# Analog_Board.net
KiCad netlist of a schematic drawn in EAGLE
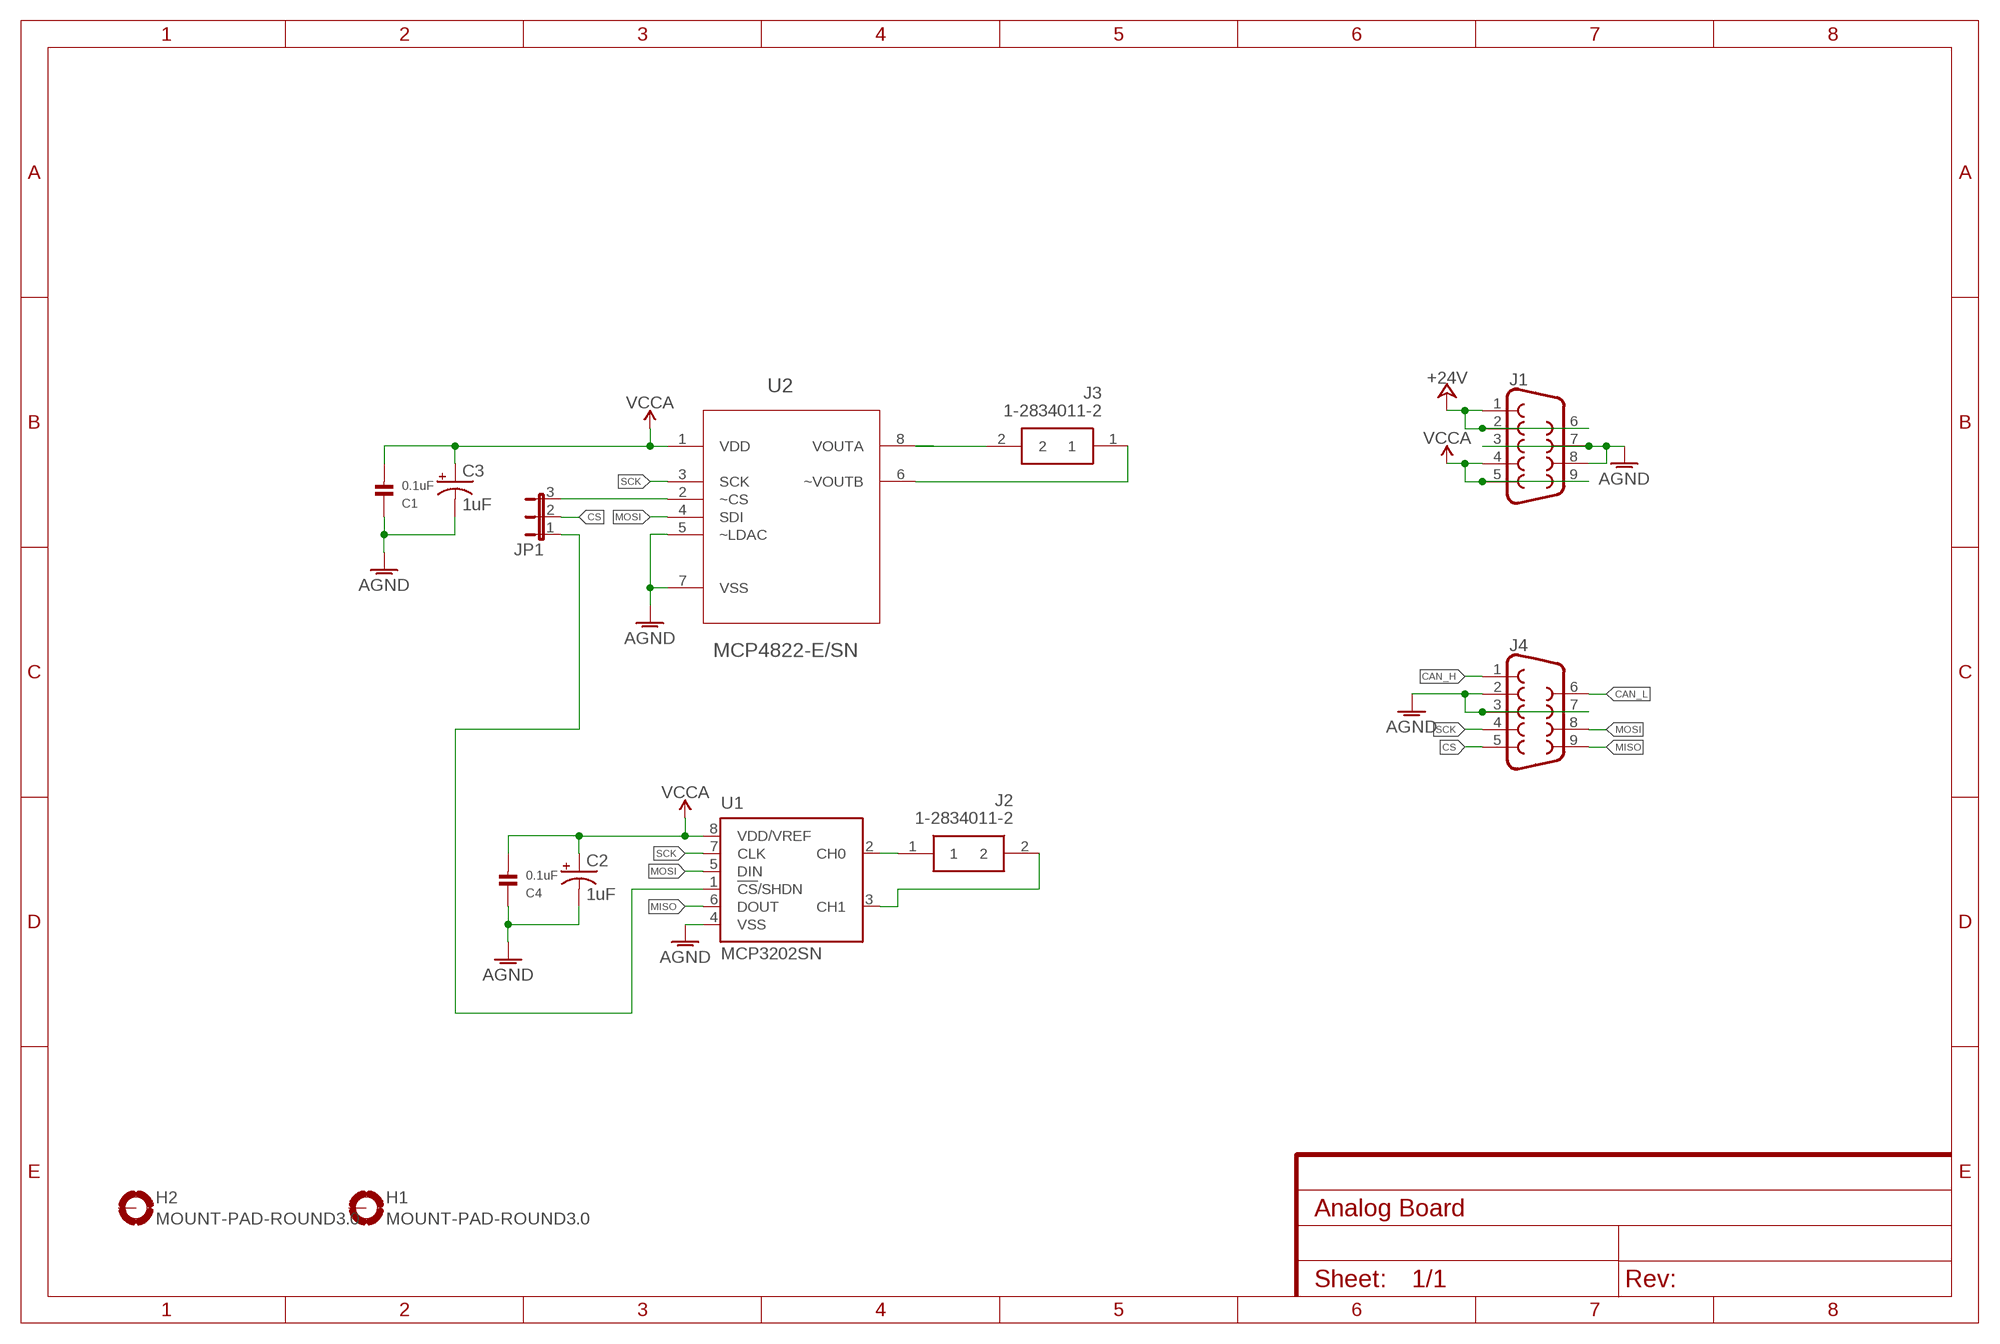
[diagram p0: schematic, sheet 1]

(export (version "E")
  (design (tool "Eeschema 10.0.6"))
  (components
    (comp (ref "C1")
      (value "0.1uF")
      (footprint "eagle-import:0805_NOTHERMALS")
      (libsource (lib "eagle-import") (part "CAP_CERAMIC0805-NOTHERMALS"))
    )
    (comp (ref "C2")
      (value "1uF")
      (footprint "eagle-import:PANASONIC_B")
      (libsource (lib "eagle-import") (part "CPOL-USB"))
    )
    (comp (ref "C3")
      (value "1uF")
      (footprint "eagle-import:PANASONIC_B")
      (libsource (lib "eagle-import") (part "CPOL-USB"))
    )
    (comp (ref "C4")
      (value "0.1uF")
      (footprint "eagle-import:0805_NOTHERMALS")
      (libsource (lib "eagle-import") (part "CAP_CERAMIC0805-NOTHERMALS"))
    )
    (comp (ref "H1")
      (value "MOUNT-PAD-ROUND3.0")
      (footprint "eagle-import:3,0-PAD")
      (libsource (lib "eagle-import") (part "MOUNT-PAD-ROUND3.0"))
    )
    (comp (ref "H2")
      (value "MOUNT-PAD-ROUND3.0")
      (footprint "eagle-import:3,0-PAD")
      (libsource (lib "eagle-import") (part "MOUNT-PAD-ROUND3.0"))
    )
    (comp (ref "J1")
      (value "DB9FEMALE")
      (footprint "eagle-import:DB9")
      (libsource (lib "eagle-import") (part "DB9FEMALE"))
    )
    (comp (ref "J2")
      (value "1-2834011-2")
      (footprint "eagle-import:128340112")
      (fields (field (name "RS_PART_NUMBER") "1649131"))
      (libsource (lib "eagle-import") (part "1-2834011-2"))
    )
    (comp (ref "J3")
      (value "1-2834011-2")
      (footprint "eagle-import:128340112")
      (fields (field (name "RS_PART_NUMBER") "1649131"))
      (libsource (lib "eagle-import") (part "1-2834011-2"))
    )
    (comp (ref "J4")
      (value "DB9FEMALE")
      (footprint "eagle-import:DB9")
      (libsource (lib "eagle-import") (part "DB9FEMALE"))
    )
    (comp (ref "JP1")
      (value "JP2W")
      (footprint "eagle-import:JP2W")
      (libsource (lib "eagle-import") (part "JP2W"))
    )
    (comp (ref "U1")
      (value "MCP3202SN")
      (footprint "eagle-import:SO-08")
      (fields (field (name "MF") "MICROCHIP") (field (name "MPN") "MCP3202-CI/SN"))
      (libsource (lib "eagle-import") (part "MCP3202SN"))
    )
    (comp (ref "U2")
      (value "MCP4822-E/SN")
      (footprint "eagle-import:SOIC8-N_MC")
      (fields (field (name "MF") "Microchip"))
      (libsource (lib "eagle-import") (part "MCP4822-E/SN"))
    )
  )
  (nets
    (net (code "1") (name "+24V") (class "Default")
      (node (ref "J1") (pin "1") (pinfunction "1_1") (pintype "passive"))
      (node (ref "J1") (pin "2") (pinfunction "2_2") (pintype "passive"))
      (node (ref "J1") (pin "6") (pinfunction "6_6") (pintype "passive"))
    )
    (net (code "2") (name "AGND") (class "Default")
      (node (ref "C1") (pin "1") (pinfunction "P$1_1") (pintype "passive"))
      (node (ref "C2") (pin "-") (pinfunction "-_-") (pintype "passive"))
      (node (ref "C3") (pin "-") (pinfunction "-_-") (pintype "passive"))
      (node (ref "C4") (pin "1") (pinfunction "P$1_1") (pintype "passive"))
      (node (ref "J1") (pin "3") (pinfunction "3_3") (pintype "passive"))
      (node (ref "J1") (pin "7") (pinfunction "7_7") (pintype "passive"))
      (node (ref "J1") (pin "8") (pinfunction "8_8") (pintype "passive"))
      (node (ref "J4") (pin "2") (pinfunction "2_2") (pintype "passive"))
      (node (ref "J4") (pin "3") (pinfunction "3_3") (pintype "passive"))
      (node (ref "J4") (pin "7") (pinfunction "7_7") (pintype "passive"))
      (node (ref "U1") (pin "4") (pinfunction "VSS_4") (pintype "input"))
      (node (ref "U2") (pin "5") (pinfunction "~{LDAC}_5") (pintype "input"))
      (node (ref "U2") (pin "7") (pinfunction "VSS_7") (pintype "power_in"))
    )
    (net (code "3") (name "CAN_H") (class "Default")
      (node (ref "J4") (pin "1") (pinfunction "1_1") (pintype "passive"))
    )
    (net (code "4") (name "CAN_L") (class "Default")
      (node (ref "J4") (pin "6") (pinfunction "6_6") (pintype "passive"))
    )
    (net (code "5") (name "CS") (class "Default")
      (node (ref "J4") (pin "5") (pinfunction "5_5") (pintype "passive"))
      (node (ref "JP1") (pin "2") (pinfunction "2_2") (pintype "passive"))
    )
    (net (code "6") (name "MISO") (class "Default")
      (node (ref "J4") (pin "9") (pinfunction "9_9") (pintype "passive"))
      (node (ref "U1") (pin "6") (pinfunction "DOUT_6") (pintype "input"))
    )
    (net (code "7") (name "MOSI") (class "Default")
      (node (ref "J4") (pin "8") (pinfunction "8_8") (pintype "passive"))
      (node (ref "U1") (pin "5") (pinfunction "DIN_5") (pintype "input"))
      (node (ref "U2") (pin "4") (pinfunction "SDI_4") (pintype "input"))
    )
    (net (code "8") (name "Net-(U1-CH0)") (class "Default")
      (node (ref "J2") (pin "1") (pinfunction "1_1") (pintype "bidirectional"))
      (node (ref "U1") (pin "2") (pinfunction "CH0_2") (pintype "input"))
    )
    (net (code "9") (name "Net-(U1-CH1)") (class "Default")
      (node (ref "J2") (pin "2") (pinfunction "2_2") (pintype "bidirectional"))
      (node (ref "U1") (pin "3") (pinfunction "CH1_3") (pintype "input"))
    )
    (net (code "10") (name "Net-(U1-~{CS}{slash}SHDN)") (class "Default")
      (node (ref "JP1") (pin "1") (pinfunction "1_1") (pintype "passive"))
      (node (ref "U1") (pin "1") (pinfunction "~{CS}/SHDN_1") (pintype "input"))
    )
    (net (code "11") (name "Net-(U2-VOUTA)") (class "Default")
      (node (ref "J3") (pin "2") (pinfunction "2_2") (pintype "bidirectional"))
      (node (ref "U2") (pin "8") (pinfunction "VOUTA_8") (pintype "output"))
    )
    (net (code "12") (name "Net-(U2-~{CS})") (class "Default")
      (node (ref "JP1") (pin "3") (pinfunction "3_3") (pintype "passive"))
      (node (ref "U2") (pin "2") (pinfunction "~{CS}_2") (pintype "input"))
    )
    (net (code "13") (name "Net-(U2-~{VOUTB})") (class "Default")
      (node (ref "J3") (pin "1") (pinfunction "1_1") (pintype "bidirectional"))
      (node (ref "U2") (pin "6") (pinfunction "~{VOUTB}_6") (pintype "input"))
    )
    (net (code "14") (name "SCK") (class "Default")
      (node (ref "J4") (pin "4") (pinfunction "4_4") (pintype "passive"))
      (node (ref "U1") (pin "7") (pinfunction "CLK_7") (pintype "input"))
      (node (ref "U2") (pin "3") (pinfunction "SCK_3") (pintype "input"))
    )
    (net (code "15") (name "VCCA") (class "Default")
      (node (ref "C1") (pin "2") (pinfunction "P$2_2") (pintype "passive"))
      (node (ref "C2") (pin "+") (pinfunction "+_+") (pintype "passive"))
      (node (ref "C3") (pin "+") (pinfunction "+_+") (pintype "passive"))
      (node (ref "C4") (pin "2") (pinfunction "P$2_2") (pintype "passive"))
      (node (ref "J1") (pin "4") (pinfunction "4_4") (pintype "passive"))
      (node (ref "J1") (pin "5") (pinfunction "5_5") (pintype "passive"))
      (node (ref "J1") (pin "9") (pinfunction "9_9") (pintype "passive"))
      (node (ref "U1") (pin "8") (pinfunction "VDD/VREF_8") (pintype "input"))
      (node (ref "U2") (pin "1") (pinfunction "VDD_1") (pintype "power_in"))
    )
    (net (code "16") (name "unconnected-(H1-MOUNT-PadB3,0)") (class "Default")
      (node (ref "H1") (pin "B3,0") (pinfunction "MOUNT_B3,0") (pintype "passive"))
    )
    (net (code "17") (name "unconnected-(H2-MOUNT-PadB3,0)") (class "Default")
      (node (ref "H2") (pin "B3,0") (pinfunction "MOUNT_B3,0") (pintype "passive"))
    )
  )
)
